# OpenSwitch.net
KiCad netlist of a schematic drawn in Altium Designer
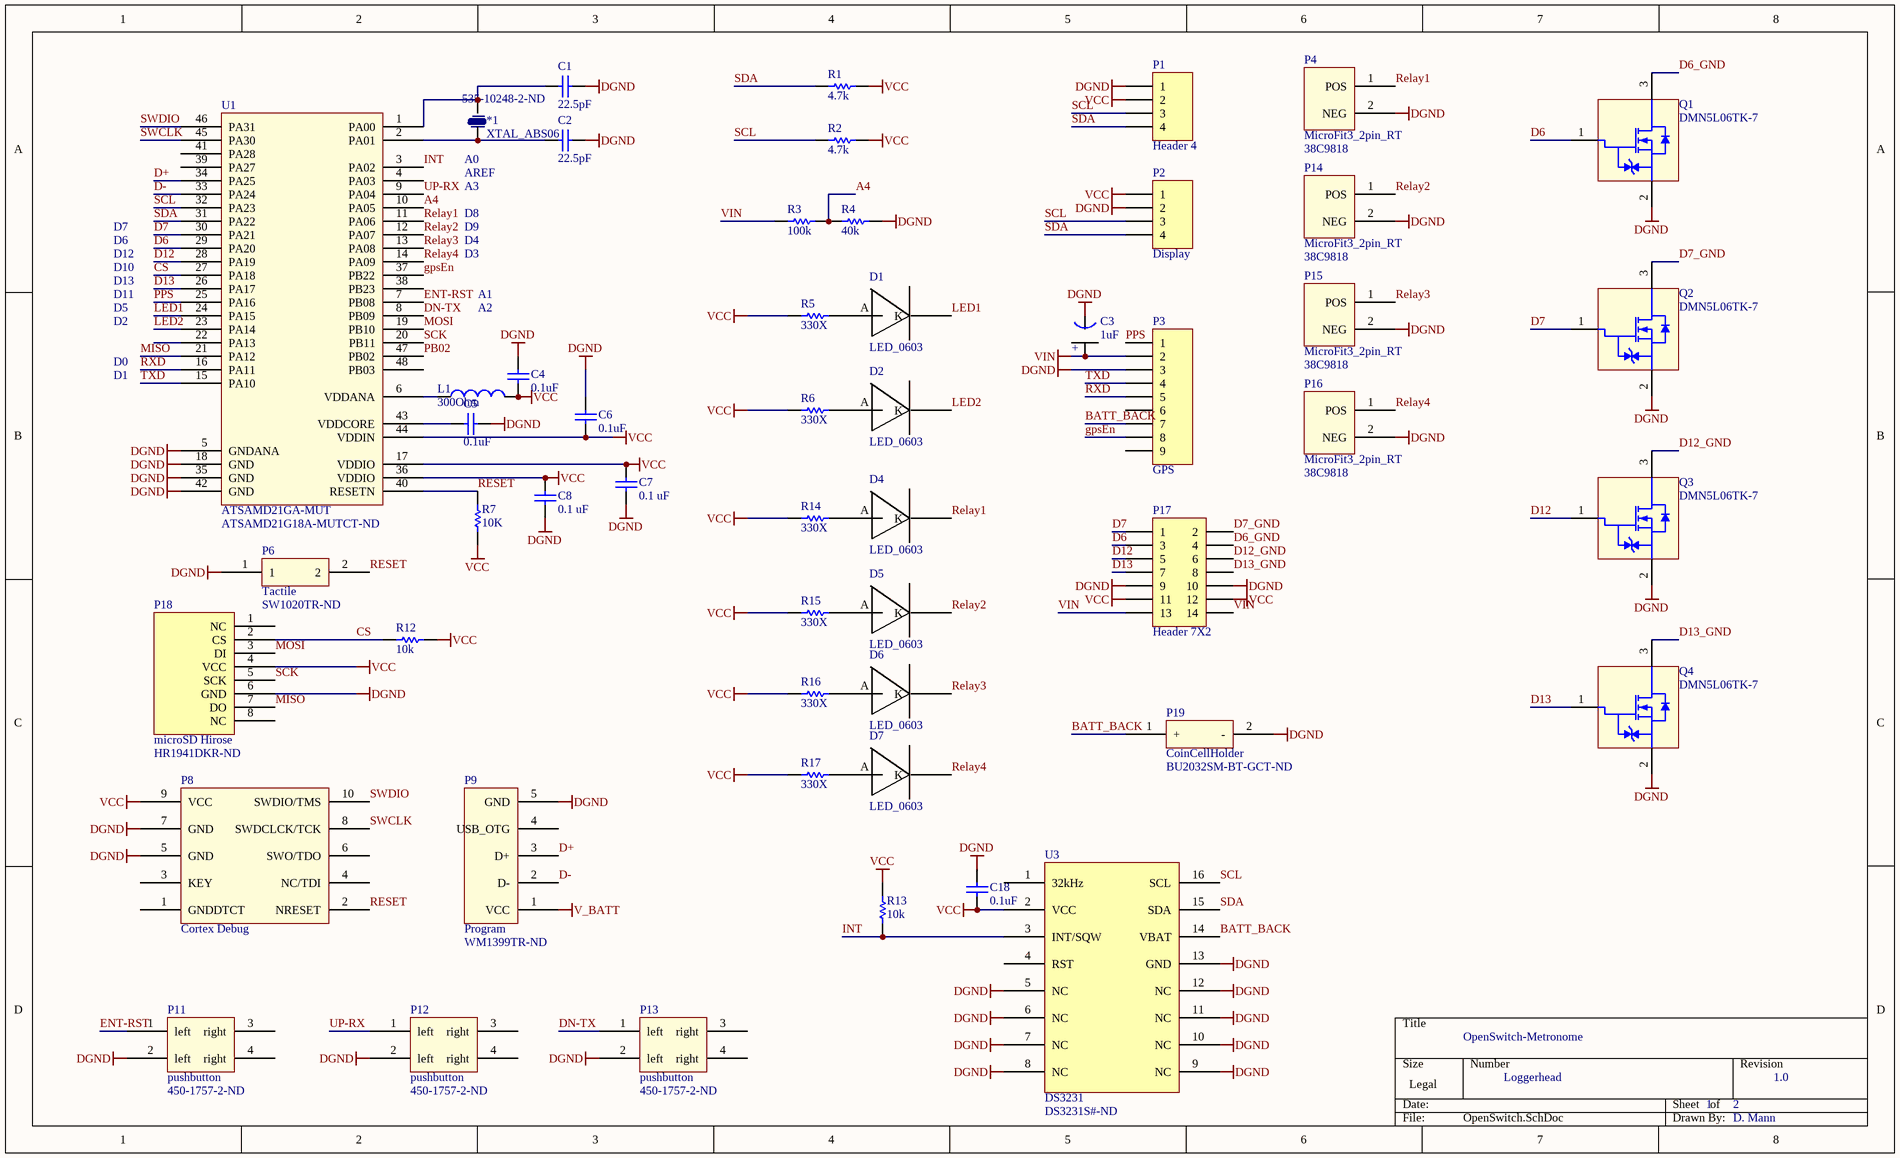
[diagram p0: OpenSwitch.SchDoc]

(export (version "E")
  (design (tool "Eeschema 10.0.6"))
  (components
    (comp (ref "*1")
      (value "XTAL_ABS06")
      (footprint "XTAL-ABS06")
      (fields (field (name "SUPPLIER PART NUMBER 1") "535-10248-2-ND"))
      (libsource (lib "Loggerhead") (part "XTAL_ABS06"))
    )
    (comp (ref "C1")
      (value "22.5pF")
      (footprint "0402")
      (description "Ceramic Chip Capacitor - Standard")
      (fields (field (name "PUBLISHER") "Altium Limited"))
      (libsource (lib "KEMET Chip Capacitor") (part "C0402"))
    )
    (comp (ref "C2")
      (value "22.5pF")
      (footprint "0402")
      (description "Ceramic Chip Capacitor - Standard")
      (fields (field (name "PUBLISHER") "Altium Limited"))
      (libsource (lib "KEMET Chip Capacitor") (part "C0402"))
    )
    (comp (ref "C3") (value "1uF") (footprint "Tant0805") (libsource (lib "Loggerhead") (part "Tant0805")))
    (comp (ref "C4")
      (value "0.1uF")
      (footprint "0402")
      (description "Ceramic Chip Capacitor - Standard")
      (fields (field (name "PUBLISHER") "Altium Limited"))
      (libsource (lib "KEMET Chip Capacitor") (part "C0402"))
    )
    (comp (ref "C5")
      (value "0.1uF")
      (footprint "0402")
      (description "Ceramic Chip Capacitor - Standard")
      (fields (field (name "PUBLISHER") "Altium Limited"))
      (libsource (lib "KEMET Chip Capacitor") (part "C0402"))
    )
    (comp (ref "C6")
      (value "0.1uF")
      (footprint "0402")
      (description "Ceramic Chip Capacitor - Standard")
      (fields (field (name "PUBLISHER") "Altium Limited"))
      (libsource (lib "KEMET Chip Capacitor") (part "C0402"))
    )
    (comp (ref "C7")
      (value "0.1 uF")
      (footprint "0402")
      (description "Ceramic Chip Capacitor - Standard")
      (fields (field (name "PUBLISHER") "Altium Limited"))
      (libsource (lib "KEMET Chip Capacitor") (part "C0402"))
    )
    (comp (ref "C8")
      (value "0.1 uF")
      (footprint "0402")
      (description "Ceramic Chip Capacitor - Standard")
      (fields (field (name "PUBLISHER") "Altium Limited"))
      (libsource (lib "KEMET Chip Capacitor") (part "C0402"))
    )
    (comp (ref "C18")
      (value "0.1uF")
      (footprint "0402")
      (description "Ceramic Chip Capacitor - Standard")
      (fields (field (name "PUBLISHER") "Altium Limited"))
      (libsource (lib "KEMET Chip Capacitor") (part "C0402"))
    )
    (comp (ref "D1")
      (value "LED_0603")
      (footprint "Diode0603")
      (libsource (lib "Loggerhead") (part "LED_0603"))
    )
    (comp (ref "D2")
      (value "LED_0603")
      (footprint "Diode0603")
      (libsource (lib "Loggerhead") (part "LED_0603"))
    )
    (comp (ref "D4")
      (value "LED_0603")
      (footprint "Diode0603")
      (libsource (lib "Loggerhead") (part "LED_0603"))
    )
    (comp (ref "D5")
      (value "LED_0603")
      (footprint "Diode0603")
      (libsource (lib "Loggerhead") (part "LED_0603"))
    )
    (comp (ref "D6")
      (value "LED_0603")
      (footprint "Diode0603")
      (libsource (lib "Loggerhead") (part "LED_0603"))
    )
    (comp (ref "D7")
      (value "LED_0603")
      (footprint "Diode0603")
      (libsource (lib "Loggerhead") (part "LED_0603"))
    )
    (comp (ref "L1")
      (value "300Ohm")
      (footprint "0805 (M2125) Ferrite")
      (description "Ferrite 25mOhm@DC,  60 Ohm@100MHz")
      (fields
        (field (name "CREATOR AND DATE") "Design Engineer's Name")
        (field (name "FOOTPRINT VERIFIED BY") "*")
        (field (name "SCHEMATIC VERIFIED BY") "*")
        (field (name "VENDOR INFO VERIFIED BY") "*")
      )
      (libsource (lib "Flanery") (part "Ferrite 0805(M2125) 3A"))
    )
    (comp (ref "P1")
      (value "Header 4")
      (footprint "HDR1X4")
      (description "Header, 4-Pin")
      (fields (field (name "PUBLISHER") "Altium Limited"))
      (libsource (lib "Miscellaneous Connectors") (part "Header 4"))
    )
    (comp (ref "P2")
      (value "Display")
      (footprint "HDR1X4")
      (description "Header, 4-Pin")
      (fields (field (name "PUBLISHER") "Altium Limited"))
      (libsource (lib "Miscellaneous Connectors") (part "Header 4"))
    )
    (comp (ref "P3")
      (value "GPS")
      (footprint "HDR1X9")
      (description "Header, 9-Pin")
      (fields (field (name "PUBLISHER") "Altium Limited"))
      (libsource (lib "Miscellaneous Connectors") (part "Header 9"))
    )
    (comp (ref "P4")
      (value "MicroFit3_2pin_RT")
      (footprint "Microfit 3 - 2 pin RT")
      (fields (field (name "SUPPLIER PART NUMBER 1") "38C9818"))
      (libsource (lib "Loggerhead") (part "MicroFit3_2pin_RT"))
    )
    (comp (ref "P6")
      (value "Tactile")
      (footprint "Tactile-B3U-1000")
      (fields (field (name "SUPPLIER PART NUMBER 1") "SW1020TR-ND"))
      (libsource (lib "Loggerhead") (part "Tactile_B3U-1000"))
    )
    (comp (ref "P8")
      (value "Cortex Debug")
      (footprint "Header_2x5_50mil")
      (libsource (lib "Loggerhead") (part "CortexDebug"))
    )
    (comp (ref "P9")
      (value "Program")
      (footprint "microUSB-B")
      (fields (field (name "SUPPLIER PART NUMBER 1") "WM1399TR-ND"))
      (libsource (lib "Loggerhead") (part "microUSB-B"))
    )
    (comp (ref "P11")
      (value "pushbutton")
      (footprint "SOP4")
      (fields (field (name "SUPPLIER PART NUMBER 1") "450-1757-2-ND"))
      (libsource (lib "Loggerhead") (part "pushbutton"))
    )
    (comp (ref "P12")
      (value "pushbutton")
      (footprint "SOP4")
      (fields (field (name "SUPPLIER PART NUMBER 1") "450-1757-2-ND"))
      (libsource (lib "Loggerhead") (part "pushbutton"))
    )
    (comp (ref "P13")
      (value "pushbutton")
      (footprint "SOP4")
      (fields (field (name "SUPPLIER PART NUMBER 1") "450-1757-2-ND"))
      (libsource (lib "Loggerhead") (part "pushbutton"))
    )
    (comp (ref "P14")
      (value "MicroFit3_2pin_RT")
      (footprint "Microfit 3 - 2 pin RT")
      (fields (field (name "SUPPLIER PART NUMBER 1") "38C9818"))
      (libsource (lib "Loggerhead") (part "MicroFit3_2pin_RT"))
    )
    (comp (ref "P15")
      (value "MicroFit3_2pin_RT")
      (footprint "Microfit 3 - 2 pin RT")
      (fields (field (name "SUPPLIER PART NUMBER 1") "38C9818"))
      (libsource (lib "Loggerhead") (part "MicroFit3_2pin_RT"))
    )
    (comp (ref "P16")
      (value "MicroFit3_2pin_RT")
      (footprint "Microfit 3 - 2 pin RT")
      (fields (field (name "SUPPLIER PART NUMBER 1") "38C9818"))
      (libsource (lib "Loggerhead") (part "MicroFit3_2pin_RT"))
    )
    (comp (ref "P17")
      (value "Header 7X2")
      (footprint "HDR2X7")
      (description "Header, 7-Pin, Dual row")
      (fields (field (name "PUBLISHER") "Altium Limited"))
      (libsource (lib "Miscellaneous Connectors") (part "Header 7X2"))
    )
    (comp (ref "P18")
      (value "microSD Hirose")
      (footprint "DM3D microSD")
      (fields (field (name "SUPPLIER PART NUMBER 1") "HR1941DKR-ND"))
      (libsource (lib "Loggerhead") (part "microSD Hirose"))
    )
    (comp (ref "P19")
      (value "CoinCellHolder")
      (footprint "CoinCellHolder")
      (fields (field (name "SUPPLIER PART NUMBER 1") "BU2032SM-BT-GCT-ND"))
      (libsource (lib "Loggerhead") (part "CoinCellHolder"))
    )
    (comp (ref "Q1")
      (value "DMN5L06TK-7")
      (footprint "SOT-523")
      (description "Ultra-low leakage Enhanced MOSFET")
      (fields
        (field (name "CREATOR AND DATE") "Will Flanery 2010-09-02")
        (field (name "FOOTPRINT VERIFIED BY") "*")
        (field (name "SCHEMATIC VERIFIED BY") "*")
        (field (name "VENDOR INFO VERIFIED BY") "*")
      )
      (libsource (lib "Flanery") (part "FET DMN5L06TK-7"))
    )
    (comp (ref "Q2")
      (value "DMN5L06TK-7")
      (footprint "SOT-523")
      (description "Ultra-low leakage Enhanced MOSFET")
      (fields
        (field (name "CREATOR AND DATE") "Will Flanery 2010-09-02")
        (field (name "FOOTPRINT VERIFIED BY") "*")
        (field (name "SCHEMATIC VERIFIED BY") "*")
        (field (name "VENDOR INFO VERIFIED BY") "*")
      )
      (libsource (lib "Flanery") (part "FET DMN5L06TK-7"))
    )
    (comp (ref "Q3")
      (value "DMN5L06TK-7")
      (footprint "SOT-523")
      (description "Ultra-low leakage Enhanced MOSFET")
      (fields
        (field (name "CREATOR AND DATE") "Will Flanery 2010-09-02")
        (field (name "FOOTPRINT VERIFIED BY") "*")
        (field (name "SCHEMATIC VERIFIED BY") "*")
        (field (name "VENDOR INFO VERIFIED BY") "*")
      )
      (libsource (lib "Flanery") (part "FET DMN5L06TK-7"))
    )
    (comp (ref "Q4")
      (value "DMN5L06TK-7")
      (footprint "SOT-523")
      (description "Ultra-low leakage Enhanced MOSFET")
      (fields
        (field (name "CREATOR AND DATE") "Will Flanery 2010-09-02")
        (field (name "FOOTPRINT VERIFIED BY") "*")
        (field (name "SCHEMATIC VERIFIED BY") "*")
        (field (name "VENDOR INFO VERIFIED BY") "*")
      )
      (libsource (lib "Flanery") (part "FET DMN5L06TK-7"))
    )
    (comp (ref "R1")
      (value "4.7k")
      (footprint "3-0603")
      (fields (field (name "PUBLISHER") "Altium Limited"))
      (libsource (lib "Panasonic Resistor") (part "ERJ3RK"))
    )
    (comp (ref "R2")
      (value "4.7k")
      (footprint "3-0603")
      (fields (field (name "PUBLISHER") "Altium Limited"))
      (libsource (lib "Panasonic Resistor") (part "ERJ3RK"))
    )
    (comp (ref "R3")
      (value "100k")
      (footprint "3-0603")
      (fields (field (name "PUBLISHER") "Altium Limited"))
      (libsource (lib "Panasonic Resistor") (part "ERJ3RK"))
    )
    (comp (ref "R4")
      (value "40k")
      (footprint "3-0603")
      (fields (field (name "PUBLISHER") "Altium Limited"))
      (libsource (lib "Panasonic Resistor") (part "ERJ3RK"))
    )
    (comp (ref "R5")
      (value "330X")
      (footprint "3-0603")
      (fields (field (name "PUBLISHER") "Altium Limited"))
      (libsource (lib "Panasonic Resistor") (part "ERJ3RK"))
    )
    (comp (ref "R6")
      (value "330X")
      (footprint "3-0603")
      (fields (field (name "PUBLISHER") "Altium Limited"))
      (libsource (lib "Panasonic Resistor") (part "ERJ3RK"))
    )
    (comp (ref "R7")
      (value "10K")
      (footprint "3-0603")
      (fields (field (name "PUBLISHER") "Altium Limited"))
      (libsource (lib "Panasonic Resistor") (part "ERJ3RK"))
    )
    (comp (ref "R12")
      (value "10k")
      (footprint "3-0603")
      (fields (field (name "PUBLISHER") "Altium Limited"))
      (libsource (lib "Panasonic Resistor") (part "ERJ3RK"))
    )
    (comp (ref "R13")
      (value "10k")
      (footprint "3-0603")
      (fields (field (name "PUBLISHER") "Altium Limited"))
      (libsource (lib "Panasonic Resistor") (part "ERJ3RK"))
    )
    (comp (ref "R14")
      (value "330X")
      (footprint "3-0603")
      (fields (field (name "PUBLISHER") "Altium Limited"))
      (libsource (lib "Panasonic Resistor") (part "ERJ3RK"))
    )
    (comp (ref "R15")
      (value "330X")
      (footprint "3-0603")
      (fields (field (name "PUBLISHER") "Altium Limited"))
      (libsource (lib "Panasonic Resistor") (part "ERJ3RK"))
    )
    (comp (ref "R16")
      (value "330X")
      (footprint "3-0603")
      (fields (field (name "PUBLISHER") "Altium Limited"))
      (libsource (lib "Panasonic Resistor") (part "ERJ3RK"))
    )
    (comp (ref "R17")
      (value "330X")
      (footprint "3-0603")
      (fields (field (name "PUBLISHER") "Altium Limited"))
      (libsource (lib "Panasonic Resistor") (part "ERJ3RK"))
    )
    (comp (ref "U1")
      (value "ATSAMD21GA-MUT")
      (footprint "QFN127P600-8N")
      (fields (field (name "SUPPLIER PART NUMBER 1") "ATSAMD21G18A-MUTCT-ND"))
      (libsource (lib "Loggerhead") (part "ATSAMD21G18"))
    )
    (comp (ref "U3")
      (value "DS3231")
      (footprint "DS3231")
      (fields (field (name "SUPPLIER PART NUMBER 1") "DS3231S#-ND"))
      (libsource (lib "Loggerhead") (part "DS3231"))
    )
  )
  (nets
    (net (code "1") (name "/A4") (class "Default")
      (node (ref "R3") (pin "1") (pinfunction "1_1") (pintype "passive"))
      (node (ref "R4") (pin "2") (pinfunction "2_2") (pintype "passive"))
      (node (ref "U1") (pin "10") (pinfunction "PA05_10") (pintype "passive"))
    )
    (net (code "2") (name "/BATT_BACK") (class "Default")
      (node (ref "P19") (pin "1") (pinfunction "+_1") (pintype "passive"))
      (node (ref "P3") (pin "7") (pinfunction "7_7") (pintype "passive"))
      (node (ref "U3") (pin "14") (pinfunction "VBAT_14") (pintype "power_in"))
    )
    (net (code "3") (name "/CS") (class "Default")
      (node (ref "P18") (pin "2") (pinfunction "CS_2") (pintype "passive"))
      (node (ref "R12") (pin "2") (pinfunction "2_2") (pintype "passive"))
      (node (ref "U1") (pin "27") (pinfunction "PA18_27") (pintype "passive"))
    )
    (net (code "4") (name "/D+") (class "Default")
      (node (ref "P9") (pin "3") (pinfunction "D+_3") (pintype "passive"))
      (node (ref "U1") (pin "34") (pinfunction "PA25_34") (pintype "passive"))
    )
    (net (code "5") (name "/D-") (class "Default")
      (node (ref "P9") (pin "2") (pinfunction "D-_2") (pintype "passive"))
      (node (ref "U1") (pin "33") (pinfunction "PA24_33") (pintype "passive"))
    )
    (net (code "6") (name "/D6") (class "Default")
      (node (ref "P17") (pin "3") (pinfunction "3_3") (pintype "passive"))
      (node (ref "Q1") (pin "1") (pinfunction "G_1") (pintype "passive"))
      (node (ref "U1") (pin "29") (pinfunction "PA20_29") (pintype "passive"))
    )
    (net (code "7") (name "/D6_GND") (class "Default")
      (node (ref "P17") (pin "4") (pinfunction "4_4") (pintype "passive"))
      (node (ref "Q1") (pin "3") (pinfunction "D_3") (pintype "passive"))
    )
    (net (code "8") (name "/D7") (class "Default")
      (node (ref "P17") (pin "1") (pinfunction "1_1") (pintype "passive"))
      (node (ref "Q2") (pin "1") (pinfunction "G_1") (pintype "passive"))
      (node (ref "U1") (pin "30") (pinfunction "PA21_30") (pintype "passive"))
    )
    (net (code "9") (name "/D7_GND") (class "Default")
      (node (ref "P17") (pin "2") (pinfunction "2_2") (pintype "passive"))
      (node (ref "Q2") (pin "3") (pinfunction "D_3") (pintype "passive"))
    )
    (net (code "10") (name "/D12") (class "Default")
      (node (ref "P17") (pin "5") (pinfunction "5_5") (pintype "passive"))
      (node (ref "Q3") (pin "1") (pinfunction "G_1") (pintype "passive"))
      (node (ref "U1") (pin "28") (pinfunction "PA19_28") (pintype "passive"))
    )
    (net (code "11") (name "/D12_GND") (class "Default")
      (node (ref "P17") (pin "6") (pinfunction "6_6") (pintype "passive"))
      (node (ref "Q3") (pin "3") (pinfunction "D_3") (pintype "passive"))
    )
    (net (code "12") (name "/D13") (class "Default")
      (node (ref "P17") (pin "7") (pinfunction "7_7") (pintype "passive"))
      (node (ref "Q4") (pin "1") (pinfunction "G_1") (pintype "passive"))
      (node (ref "U1") (pin "26") (pinfunction "PA17_26") (pintype "passive"))
    )
    (net (code "13") (name "/D13_GND") (class "Default")
      (node (ref "P17") (pin "8") (pinfunction "8_8") (pintype "passive"))
      (node (ref "Q4") (pin "3") (pinfunction "D_3") (pintype "passive"))
    )
    (net (code "14") (name "/DN-TX") (class "Default")
      (node (ref "P13") (pin "1") (pinfunction "left_1") (pintype "passive"))
      (node (ref "U1") (pin "8") (pinfunction "PB09_8") (pintype "passive"))
    )
    (net (code "15") (name "/ENT-RST") (class "Default")
      (node (ref "P11") (pin "1") (pinfunction "left_1") (pintype "passive"))
      (node (ref "U1") (pin "7") (pinfunction "PB08_7") (pintype "passive"))
    )
    (net (code "16") (name "/INT") (class "Default")
      (node (ref "R13") (pin "2") (pinfunction "2_2") (pintype "passive"))
      (node (ref "U1") (pin "3") (pinfunction "PA02_3") (pintype "passive"))
      (node (ref "U3") (pin "3") (pinfunction "INT/SQW_3") (pintype "passive"))
    )
    (net (code "17") (name "/LED1") (class "Default")
      (node (ref "D1") (pin "K") (pinfunction "K_K") (pintype "passive"))
      (node (ref "U1") (pin "24") (pinfunction "PA15_24") (pintype "passive"))
    )
    (net (code "18") (name "/LED2") (class "Default")
      (node (ref "D2") (pin "K") (pinfunction "K_K") (pintype "passive"))
      (node (ref "U1") (pin "23") (pinfunction "PA14_23") (pintype "passive"))
    )
    (net (code "19") (name "/MISO") (class "Default")
      (node (ref "P18") (pin "7") (pinfunction "DO_7") (pintype "passive"))
      (node (ref "U1") (pin "21") (pinfunction "PA12_21") (pintype "passive"))
    )
    (net (code "20") (name "/MOSI") (class "Default")
      (node (ref "P18") (pin "3") (pinfunction "DI_3") (pintype "passive"))
      (node (ref "U1") (pin "19") (pinfunction "PB10_19") (pintype "passive"))
    )
    (net (code "21") (name "/PB02") (class "Default")
      (node (ref "U1") (pin "47") (pinfunction "PB02_47") (pintype "passive"))
    )
    (net (code "22") (name "/PPS") (class "Default")
      (node (ref "P3") (pin "1") (pinfunction "1_1") (pintype "passive"))
      (node (ref "U1") (pin "25") (pinfunction "PA16_25") (pintype "passive"))
    )
    (net (code "23") (name "/RESET") (class "Default")
      (node (ref "P6") (pin "2") (pinfunction "2_2") (pintype "passive"))
      (node (ref "P8") (pin "2") (pinfunction "NRESET_2") (pintype "passive"))
      (node (ref "R7") (pin "2") (pinfunction "2_2") (pintype "passive"))
      (node (ref "U1") (pin "40") (pinfunction "RESETN_40") (pintype "passive"))
    )
    (net (code "24") (name "/RXD") (class "Default")
      (node (ref "P3") (pin "5") (pinfunction "5_5") (pintype "passive"))
      (node (ref "U1") (pin "16") (pinfunction "PA11_16") (pintype "passive"))
    )
    (net (code "25") (name "/Relay1") (class "Default")
      (node (ref "D4") (pin "K") (pinfunction "K_K") (pintype "passive"))
      (node (ref "P4") (pin "1") (pinfunction "POS_1") (pintype "passive"))
      (node (ref "U1") (pin "11") (pinfunction "PA06_11") (pintype "passive"))
    )
    (net (code "26") (name "/Relay2") (class "Default")
      (node (ref "D5") (pin "K") (pinfunction "K_K") (pintype "passive"))
      (node (ref "P14") (pin "1") (pinfunction "POS_1") (pintype "passive"))
      (node (ref "U1") (pin "12") (pinfunction "PA07_12") (pintype "passive"))
    )
    (net (code "27") (name "/Relay3") (class "Default")
      (node (ref "D6") (pin "K") (pinfunction "K_K") (pintype "passive"))
      (node (ref "P15") (pin "1") (pinfunction "POS_1") (pintype "passive"))
      (node (ref "U1") (pin "13") (pinfunction "PA08_13") (pintype "passive"))
    )
    (net (code "28") (name "/Relay4") (class "Default")
      (node (ref "D7") (pin "K") (pinfunction "K_K") (pintype "passive"))
      (node (ref "P16") (pin "1") (pinfunction "POS_1") (pintype "passive"))
      (node (ref "U1") (pin "14") (pinfunction "PA09_14") (pintype "passive"))
    )
    (net (code "29") (name "/SCK") (class "Default")
      (node (ref "P18") (pin "5") (pinfunction "SCK_5") (pintype "passive"))
      (node (ref "U1") (pin "20") (pinfunction "PB11_20") (pintype "passive"))
    )
    (net (code "30") (name "/SCL") (class "Default")
      (node (ref "P1") (pin "3") (pinfunction "3_3") (pintype "passive"))
      (node (ref "P2") (pin "3") (pinfunction "3_3") (pintype "passive"))
      (node (ref "R2") (pin "1") (pinfunction "1_1") (pintype "passive"))
      (node (ref "U1") (pin "32") (pinfunction "PA23_32") (pintype "passive"))
      (node (ref "U3") (pin "16") (pinfunction "SCL_16") (pintype "passive"))
    )
    (net (code "31") (name "/SDA") (class "Default")
      (node (ref "P1") (pin "4") (pinfunction "4_4") (pintype "passive"))
      (node (ref "P2") (pin "4") (pinfunction "4_4") (pintype "passive"))
      (node (ref "R1") (pin "1") (pinfunction "1_1") (pintype "passive"))
      (node (ref "U1") (pin "31") (pinfunction "PA22_31") (pintype "passive"))
      (node (ref "U3") (pin "15") (pinfunction "SDA_15") (pintype "passive"))
    )
    (net (code "32") (name "/SWCLK") (class "Default")
      (node (ref "P8") (pin "8") (pinfunction "SWDCLCK/TCK_8") (pintype "passive"))
      (node (ref "U1") (pin "45") (pinfunction "PA30_45") (pintype "passive"))
    )
    (net (code "33") (name "/SWDIO") (class "Default")
      (node (ref "P8") (pin "10") (pinfunction "SWDIO/TMS_10") (pintype "passive"))
      (node (ref "U1") (pin "46") (pinfunction "PA31_46") (pintype "passive"))
    )
    (net (code "34") (name "/TXD") (class "Default")
      (node (ref "P3") (pin "4") (pinfunction "4_4") (pintype "passive"))
      (node (ref "U1") (pin "15") (pinfunction "PA10_15") (pintype "passive"))
    )
    (net (code "35") (name "/UP-RX") (class "Default")
      (node (ref "P12") (pin "1") (pinfunction "left_1") (pintype "passive"))
      (node (ref "U1") (pin "9") (pinfunction "PA04_9") (pintype "passive"))
    )
    (net (code "36") (name "/gpsEn") (class "Default")
      (node (ref "P3") (pin "8") (pinfunction "8_8") (pintype "passive"))
      (node (ref "U1") (pin "37") (pinfunction "PB22_37") (pintype "passive"))
    )
    (net (code "37") (name "DGND") (class "Default")
      (node (ref "C1") (pin "1") (pinfunction "1_1") (pintype "passive"))
      (node (ref "C18") (pin "2") (pinfunction "2_2") (pintype "passive"))
      (node (ref "C2") (pin "1") (pinfunction "1_1") (pintype "passive"))
      (node (ref "C3") (pin "1") (pinfunction "GND_1") (pintype "passive"))
      (node (ref "C4") (pin "2") (pinfunction "2_2") (pintype "passive"))
      (node (ref "C5") (pin "2") (pinfunction "2_2") (pintype "passive"))
      (node (ref "C6") (pin "2") (pinfunction "2_2") (pintype "passive"))
      (node (ref "C7") (pin "2") (pinfunction "2_2") (pintype "passive"))
      (node (ref "C8") (pin "2") (pinfunction "2_2") (pintype "passive"))
      (node (ref "P1") (pin "1") (pinfunction "1_1") (pintype "passive"))
      (node (ref "P11") (pin "2") (pinfunction "left_2") (pintype "passive"))
      (node (ref "P12") (pin "2") (pinfunction "left_2") (pintype "passive"))
      (node (ref "P13") (pin "2") (pinfunction "left_2") (pintype "passive"))
      (node (ref "P14") (pin "2") (pinfunction "NEG_2") (pintype "passive"))
      (node (ref "P15") (pin "2") (pinfunction "NEG_2") (pintype "passive"))
      (node (ref "P16") (pin "2") (pinfunction "NEG_2") (pintype "passive"))
      (node (ref "P17") (pin "10") (pinfunction "10_10") (pintype "passive"))
      (node (ref "P17") (pin "9") (pinfunction "9_9") (pintype "passive"))
      (node (ref "P18") (pin "6") (pinfunction "GND_6") (pintype "passive"))
      (node (ref "P19") (pin "2") (pinfunction "-_2") (pintype "passive"))
      (node (ref "P2") (pin "2") (pinfunction "2_2") (pintype "passive"))
      (node (ref "P3") (pin "3") (pinfunction "3_3") (pintype "passive"))
      (node (ref "P4") (pin "2") (pinfunction "NEG_2") (pintype "passive"))
      (node (ref "P6") (pin "1") (pinfunction "1_1") (pintype "passive"))
      (node (ref "P8") (pin "5") (pinfunction "GND_5") (pintype "passive"))
      (node (ref "P8") (pin "7") (pinfunction "GND_7") (pintype "passive"))
      (node (ref "P9") (pin "5") (pinfunction "GND_5") (pintype "passive"))
      (node (ref "Q1") (pin "2") (pinfunction "S_2") (pintype "passive"))
      (node (ref "Q2") (pin "2") (pinfunction "S_2") (pintype "passive"))
      (node (ref "Q3") (pin "2") (pinfunction "S_2") (pintype "passive"))
      (node (ref "Q4") (pin "2") (pinfunction "S_2") (pintype "passive"))
      (node (ref "R4") (pin "1") (pinfunction "1_1") (pintype "passive"))
      (node (ref "U1") (pin "18") (pinfunction "GND_18") (pintype "passive"))
      (node (ref "U1") (pin "35") (pinfunction "GND_35") (pintype "passive"))
      (node (ref "U1") (pin "42") (pinfunction "GND_42") (pintype "passive"))
      (node (ref "U1") (pin "5") (pinfunction "GNDANA_5") (pintype "passive"))
      (node (ref "U3") (pin "10") (pinfunction "NC_10") (pintype "passive"))
      (node (ref "U3") (pin "11") (pinfunction "NC_11") (pintype "passive"))
      (node (ref "U3") (pin "12") (pinfunction "NC_12") (pintype "passive"))
      (node (ref "U3") (pin "13") (pinfunction "GND_13") (pintype "passive"))
      (node (ref "U3") (pin "5") (pinfunction "NC_5") (pintype "passive"))
      (node (ref "U3") (pin "6") (pinfunction "NC_6") (pintype "passive"))
      (node (ref "U3") (pin "7") (pinfunction "NC_7") (pintype "passive"))
      (node (ref "U3") (pin "8") (pinfunction "NC_8") (pintype "passive"))
      (node (ref "U3") (pin "9") (pinfunction "NC_9") (pintype "passive"))
    )
    (net (code "38") (name "Net-(D1-PadA)") (class "Default")
      (node (ref "D1") (pin "A") (pinfunction "A_A") (pintype "passive"))
      (node (ref "R5") (pin "2") (pinfunction "2_2") (pintype "passive"))
    )
    (net (code "39") (name "Net-(D2-PadA)") (class "Default")
      (node (ref "D2") (pin "A") (pinfunction "A_A") (pintype "passive"))
      (node (ref "R6") (pin "2") (pinfunction "2_2") (pintype "passive"))
    )
    (net (code "40") (name "Net-(D4-PadA)") (class "Default")
      (node (ref "D4") (pin "A") (pinfunction "A_A") (pintype "passive"))
      (node (ref "R14") (pin "2") (pinfunction "2_2") (pintype "passive"))
    )
    (net (code "41") (name "Net-(D5-PadA)") (class "Default")
      (node (ref "D5") (pin "A") (pinfunction "A_A") (pintype "passive"))
      (node (ref "R15") (pin "2") (pinfunction "2_2") (pintype "passive"))
    )
    (net (code "42") (name "Net-(D6-PadA)") (class "Default")
      (node (ref "D6") (pin "A") (pinfunction "A_A") (pintype "passive"))
      (node (ref "R16") (pin "2") (pinfunction "2_2") (pintype "passive"))
    )
    (net (code "43") (name "Net-(D7-PadA)") (class "Default")
      (node (ref "D7") (pin "A") (pinfunction "A_A") (pintype "passive"))
      (node (ref "R17") (pin "2") (pinfunction "2_2") (pintype "passive"))
    )
    (net (code "44") (name "Net-(U1-PA00)") (class "Default")
      (node (ref "*1") (pin "2") (pinfunction "2_2") (pintype "passive"))
      (node (ref "C1") (pin "2") (pinfunction "2_2") (pintype "passive"))
      (node (ref "U1") (pin "1") (pinfunction "PA00_1") (pintype "passive"))
    )
    (net (code "45") (name "Net-(U1-PA01)") (class "Default")
      (node (ref "*1") (pin "1") (pinfunction "1_1") (pintype "passive"))
      (node (ref "C2") (pin "2") (pinfunction "2_2") (pintype "passive"))
      (node (ref "U1") (pin "2") (pinfunction "PA01_2") (pintype "passive"))
    )
    (net (code "46") (name "Net-(U1-VDDANA)") (class "Default")
      (node (ref "L1") (pin "1") (pinfunction "1_1") (pintype "passive"))
      (node (ref "U1") (pin "6") (pinfunction "VDDANA_6") (pintype "passive"))
    )
    (net (code "47") (name "Net-(U1-VDDCORE)") (class "Default")
      (node (ref "C5") (pin "1") (pinfunction "1_1") (pintype "passive"))
      (node (ref "U1") (pin "43") (pinfunction "VDDCORE_43") (pintype "passive"))
    )
    (net (code "48") (name "VCC") (class "Default")
      (node (ref "C18") (pin "1") (pinfunction "1_1") (pintype "passive"))
      (node (ref "C4") (pin "1") (pinfunction "1_1") (pintype "passive"))
      (node (ref "C6") (pin "1") (pinfunction "1_1") (pintype "passive"))
      (node (ref "C7") (pin "1") (pinfunction "1_1") (pintype "passive"))
      (node (ref "C8") (pin "1") (pinfunction "1_1") (pintype "passive"))
      (node (ref "L1") (pin "2") (pinfunction "2_2") (pintype "passive"))
      (node (ref "P1") (pin "2") (pinfunction "2_2") (pintype "passive"))
      (node (ref "P17") (pin "11") (pinfunction "11_11") (pintype "passive"))
      (node (ref "P17") (pin "12") (pinfunction "12_12") (pintype "passive"))
      (node (ref "P18") (pin "4") (pinfunction "VCC_4") (pintype "passive"))
      (node (ref "P2") (pin "1") (pinfunction "1_1") (pintype "passive"))
      (node (ref "P8") (pin "9") (pinfunction "VCC_9") (pintype "passive"))
      (node (ref "R1") (pin "2") (pinfunction "2_2") (pintype "passive"))
      (node (ref "R12") (pin "1") (pinfunction "1_1") (pintype "passive"))
      (node (ref "R13") (pin "1") (pinfunction "1_1") (pintype "passive"))
      (node (ref "R14") (pin "1") (pinfunction "1_1") (pintype "passive"))
      (node (ref "R15") (pin "1") (pinfunction "1_1") (pintype "passive"))
      (node (ref "R16") (pin "1") (pinfunction "1_1") (pintype "passive"))
      (node (ref "R17") (pin "1") (pinfunction "1_1") (pintype "passive"))
      (node (ref "R2") (pin "2") (pinfunction "2_2") (pintype "passive"))
      (node (ref "R5") (pin "1") (pinfunction "1_1") (pintype "passive"))
      (node (ref "R6") (pin "1") (pinfunction "1_1") (pintype "passive"))
      (node (ref "R7") (pin "1") (pinfunction "1_1") (pintype "passive"))
      (node (ref "U1") (pin "17") (pinfunction "VDDIO_17") (pintype "passive"))
      (node (ref "U1") (pin "36") (pinfunction "VDDIO_36") (pintype "passive"))
      (node (ref "U1") (pin "44") (pinfunction "VDDIN_44") (pintype "passive"))
      (node (ref "U3") (pin "2") (pinfunction "VCC_2") (pintype "power_in"))
    )
    (net (code "49") (name "VIN") (class "Default")
      (node (ref "C3") (pin "2") (pinfunction "+_2") (pintype "passive"))
      (node (ref "P17") (pin "13") (pinfunction "13_13") (pintype "passive"))
      (node (ref "P17") (pin "14") (pinfunction "14_14") (pintype "passive"))
      (node (ref "P3") (pin "2") (pinfunction "2_2") (pintype "passive"))
      (node (ref "R3") (pin "2") (pinfunction "2_2") (pintype "passive"))
    )
    (net (code "50") (name "V_BATT") (class "Default")
      (node (ref "P9") (pin "1") (pinfunction "VCC_1") (pintype "passive"))
    )
    (net (code "51") (name "unconnected-(P3-Pad6)") (class "Default")
      (node (ref "P3") (pin "6") (pinfunction "6_6") (pintype "passive"))
    )
    (net (code "52") (name "unconnected-(P3-Pad9)") (class "Default")
      (node (ref "P3") (pin "9") (pinfunction "9_9") (pintype "passive"))
    )
    (net (code "53") (name "unconnected-(P8-GNDDTCT-Pad1)") (class "Default")
      (node (ref "P8") (pin "1") (pinfunction "GNDDTCT_1") (pintype "passive"))
    )
    (net (code "54") (name "unconnected-(P8-KEY-Pad3)") (class "Default")
      (node (ref "P8") (pin "3") (pinfunction "KEY_3") (pintype "passive"))
    )
    (net (code "55") (name "unconnected-(P8-NC{slash}TDI-Pad4)") (class "Default")
      (node (ref "P8") (pin "4") (pinfunction "NC/TDI_4") (pintype "passive"))
    )
    (net (code "56") (name "unconnected-(P8-SWO{slash}TDO-Pad6)") (class "Default")
      (node (ref "P8") (pin "6") (pinfunction "SWO/TDO_6") (pintype "passive"))
    )
    (net (code "57") (name "unconnected-(P9-USB_OTG-Pad4)") (class "Default")
      (node (ref "P9") (pin "4") (pinfunction "USB_OTG_4") (pintype "passive"))
    )
    (net (code "58") (name "unconnected-(P11-right-Pad3)") (class "Default")
      (node (ref "P11") (pin "3") (pinfunction "right_3") (pintype "passive"))
    )
    (net (code "59") (name "unconnected-(P11-right-Pad4)") (class "Default")
      (node (ref "P11") (pin "4") (pinfunction "right_4") (pintype "passive"))
    )
    (net (code "60") (name "unconnected-(P12-right-Pad3)") (class "Default")
      (node (ref "P12") (pin "3") (pinfunction "right_3") (pintype "passive"))
    )
    (net (code "61") (name "unconnected-(P12-right-Pad4)") (class "Default")
      (node (ref "P12") (pin "4") (pinfunction "right_4") (pintype "passive"))
    )
    (net (code "62") (name "unconnected-(P13-right-Pad3)") (class "Default")
      (node (ref "P13") (pin "3") (pinfunction "right_3") (pintype "passive"))
    )
    (net (code "63") (name "unconnected-(P13-right-Pad4)") (class "Default")
      (node (ref "P13") (pin "4") (pinfunction "right_4") (pintype "passive"))
    )
    (net (code "64") (name "unconnected-(P18-NC-Pad1)") (class "Default")
      (node (ref "P18") (pin "1") (pinfunction "NC_1") (pintype "passive"))
    )
    (net (code "65") (name "unconnected-(P18-NC-Pad8)") (class "Default")
      (node (ref "P18") (pin "8") (pinfunction "NC_8") (pintype "passive"))
    )
    (net (code "66") (name "unconnected-(U1-PA03-Pad4)") (class "Default")
      (node (ref "U1") (pin "4") (pinfunction "PA03_4") (pintype "passive"))
    )
    (net (code "67") (name "unconnected-(U1-PA13-Pad22)") (class "Default")
      (node (ref "U1") (pin "22") (pinfunction "PA13_22") (pintype "passive"))
    )
    (net (code "68") (name "unconnected-(U1-PA27-Pad39)") (class "Default")
      (node (ref "U1") (pin "39") (pinfunction "PA27_39") (pintype "passive"))
    )
    (net (code "69") (name "unconnected-(U1-PA28-Pad41)") (class "Default")
      (node (ref "U1") (pin "41") (pinfunction "PA28_41") (pintype "passive"))
    )
    (net (code "70") (name "unconnected-(U1-PB03-Pad48)") (class "Default")
      (node (ref "U1") (pin "48") (pinfunction "PB03_48") (pintype "passive"))
    )
    (net (code "71") (name "unconnected-(U1-PB23-Pad38)") (class "Default")
      (node (ref "U1") (pin "38") (pinfunction "PB23_38") (pintype "passive"))
    )
    (net (code "72") (name "unconnected-(U3-32kHz-Pad1)") (class "Default")
      (node (ref "U3") (pin "1") (pinfunction "32kHz_1") (pintype "passive"))
    )
    (net (code "73") (name "unconnected-(U3-RST-Pad4)") (class "Default")
      (node (ref "U3") (pin "4") (pinfunction "RST_4") (pintype "passive"))
    )
  )
)
